# ETH-PHY.net
KiCad netlist of a schematic drawn in Altium Designer
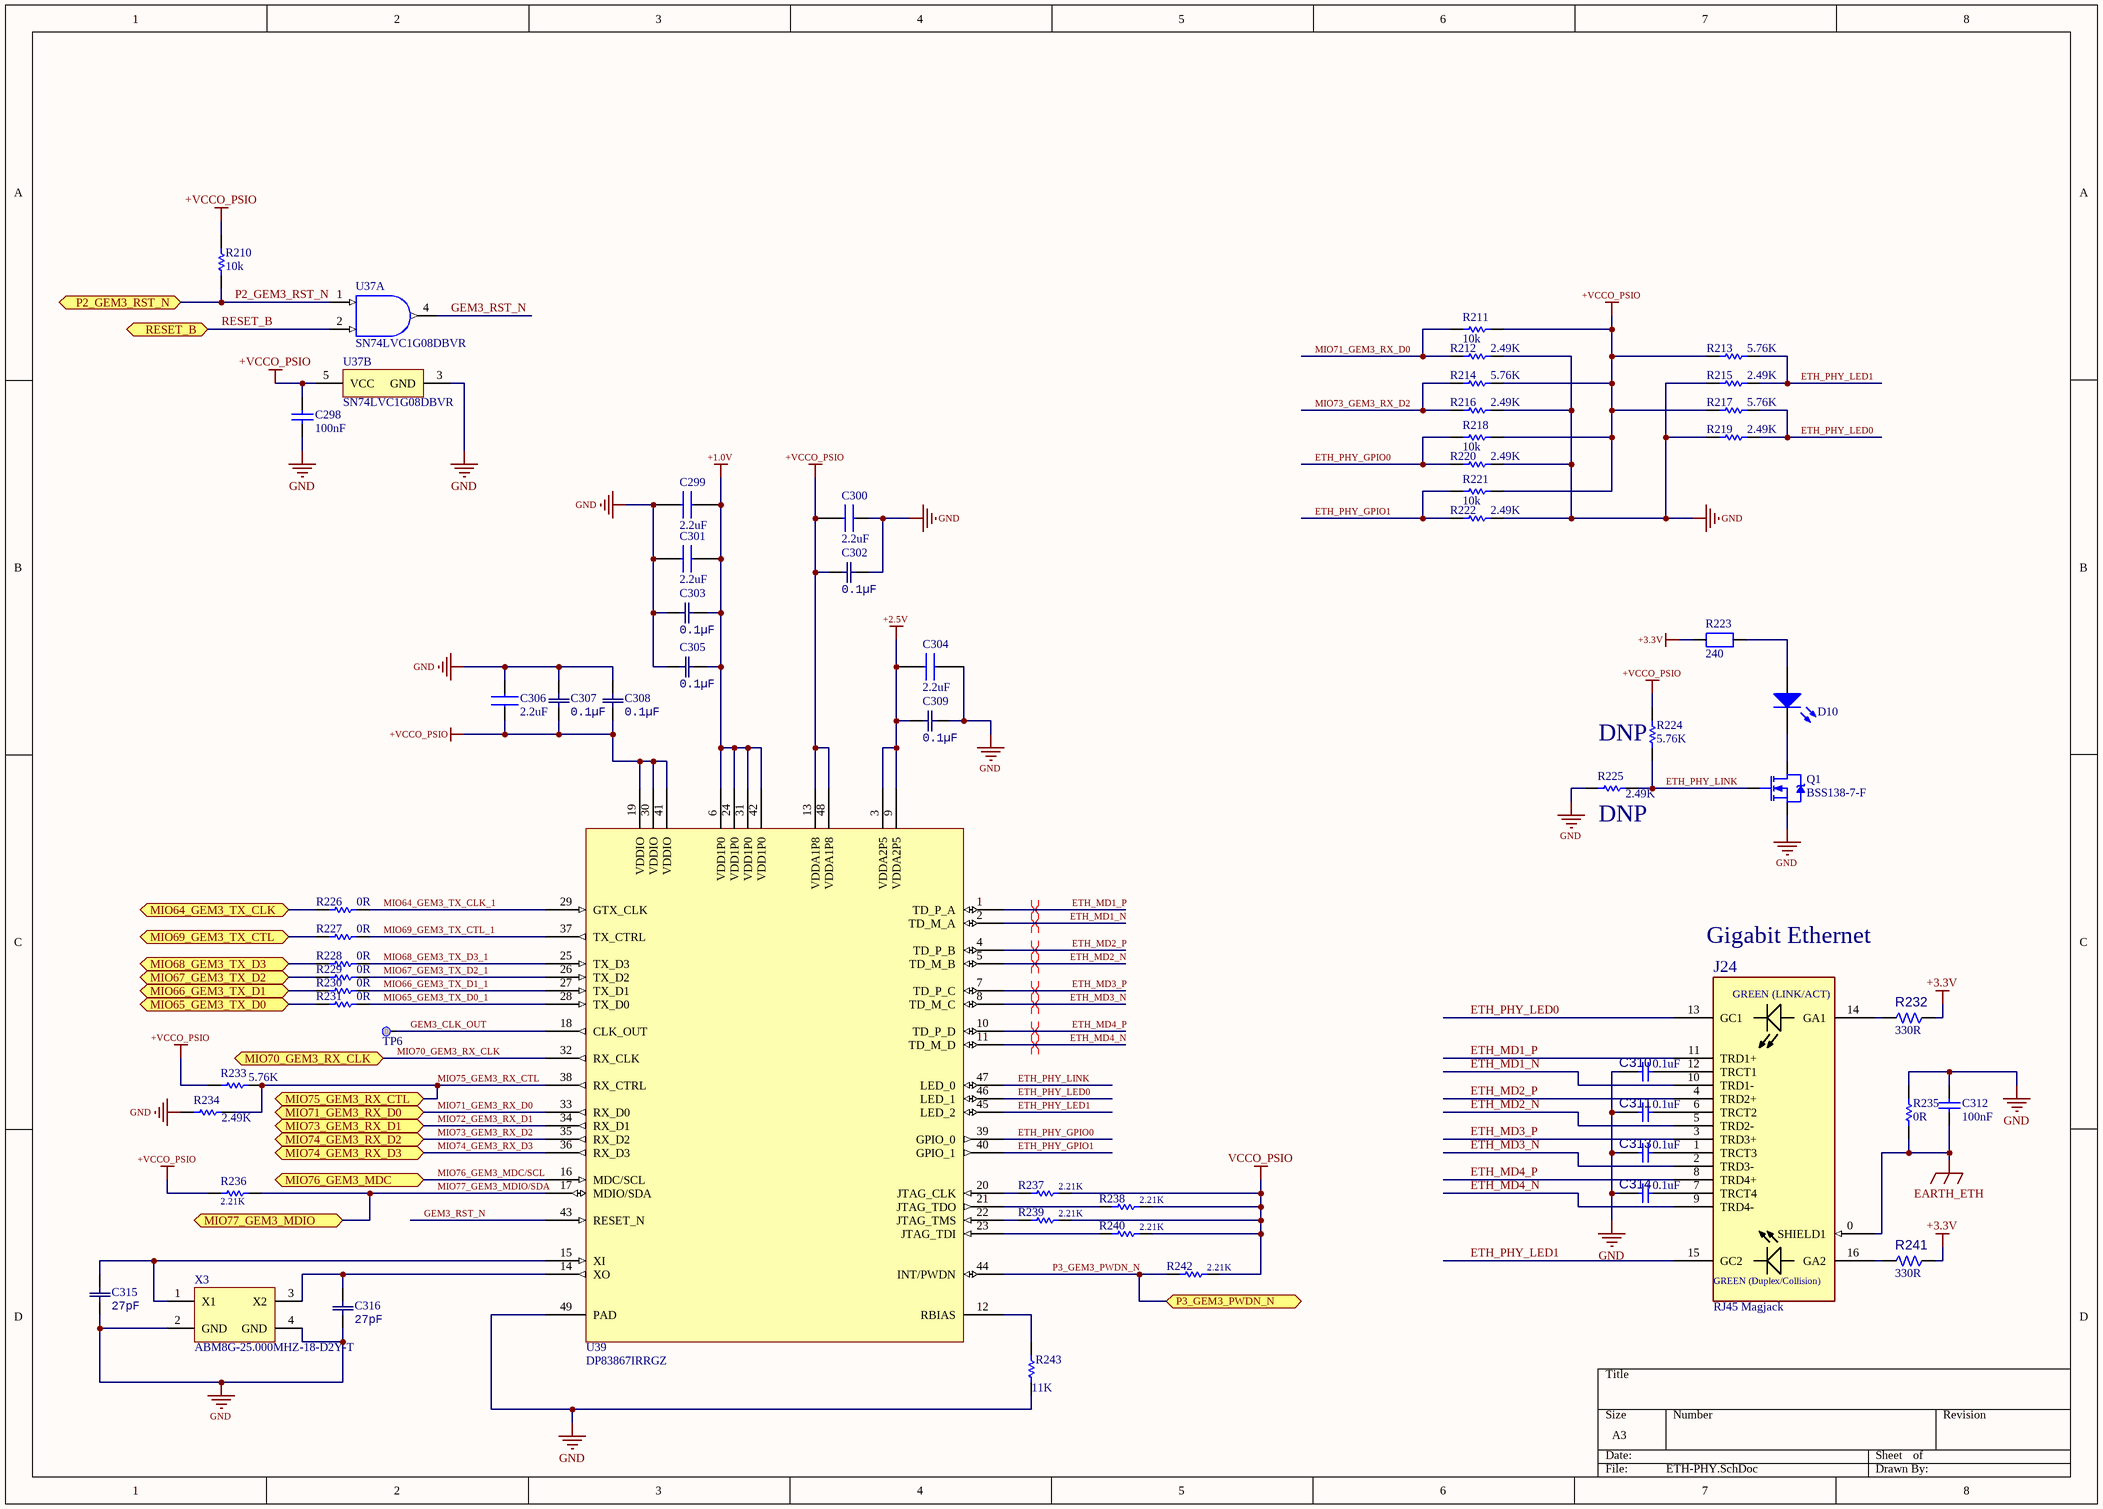
[diagram p0: ETH-PHY.SchDoc]

(export (version "E")
  (design (tool "Eeschema 10.0.6"))
  (components
    (comp (ref "C298")
      (value "100nF")
      (footprint "CAPC1005L_0402")
      (description "CAP CER 0.1UF 25V X7R 0402")
      (fields (field (name "VOLTAGE") "25V") (field (name "TOLERANCE") "10%"))
      (libsource (lib "Ultrascale_SchLib") (part "CAPCER0402X7R100N25V_10T"))
    )
    (comp (ref "C299")
      (value "2.2uF")
      (footprint "CAPC0603X33N")
      (description "Multilayer Ceramic Capacitors MLCC - SMD/SMT 0201 2.2uF 10volts *Derate Voltage/Temp")
      (fields (field (name "MANUFACTURER_PART_NUMBER") "GRM033R61A225KE47D"))
      (libsource (lib "Ultrascale_SchLib") (part "GRM033R61A225KE47D"))
    )
    (comp (ref "C300")
      (value "2.2uF")
      (footprint "CAPC0603X33N")
      (description "Multilayer Ceramic Capacitors MLCC - SMD/SMT 0201 2.2uF 10volts *Derate Voltage/Temp")
      (fields (field (name "MANUFACTURER_PART_NUMBER") "GRM033R61A225KE47D"))
      (libsource (lib "Ultrascale_SchLib") (part "GRM033R61A225KE47D"))
    )
    (comp (ref "C301")
      (value "2.2uF")
      (footprint "CAPC0603X33N")
      (description "Multilayer Ceramic Capacitors MLCC - SMD/SMT 0201 2.2uF 10volts *Derate Voltage/Temp")
      (fields (field (name "MANUFACTURER_PART_NUMBER") "GRM033R61A225KE47D"))
      (libsource (lib "Ultrascale_SchLib") (part "GRM033R61A225KE47D"))
    )
    (comp (ref "C302")
      (value "0.1µF")
      (footprint "CAP_0603")
      (description "CAP CER 0.1UF 25V 10% X5R 0201")
      (fields
        (field (name "MANUFACTURER_PART_NUMBER") "C0603X5R1E104K030BB")
        (field (name "DIGI-KEY PART NUMBER") "445-13671-1-ND")
      )
      (libsource (lib "Ultrascale_SchLib") (part "C0603X5R1E104K030BB"))
    )
    (comp (ref "C303")
      (value "0.1µF")
      (footprint "CAP_0603")
      (description "CAP CER 0.1UF 25V 10% X5R 0201")
      (fields
        (field (name "MANUFACTURER_PART_NUMBER") "C0603X5R1E104K030BB")
        (field (name "DIGI-KEY PART NUMBER") "445-13671-1-ND")
      )
      (libsource (lib "Ultrascale_SchLib") (part "C0603X5R1E104K030BB"))
    )
    (comp (ref "C304")
      (value "2.2uF")
      (footprint "CAPC0603X33N")
      (description "Multilayer Ceramic Capacitors MLCC - SMD/SMT 0201 2.2uF 10volts *Derate Voltage/Temp")
      (fields (field (name "MANUFACTURER_PART_NUMBER") "GRM033R61A225KE47D"))
      (libsource (lib "Ultrascale_SchLib") (part "GRM033R61A225KE47D"))
    )
    (comp (ref "C305")
      (value "0.1µF")
      (footprint "CAP_0603")
      (description "CAP CER 0.1UF 25V 10% X5R 0201")
      (fields
        (field (name "MANUFACTURER_PART_NUMBER") "C0603X5R1E104K030BB")
        (field (name "DIGI-KEY PART NUMBER") "445-13671-1-ND")
      )
      (libsource (lib "Ultrascale_SchLib") (part "C0603X5R1E104K030BB"))
    )
    (comp (ref "C306")
      (value "2.2uF")
      (footprint "CAPC0603X33N")
      (description "Multilayer Ceramic Capacitors MLCC - SMD/SMT 0201 2.2uF 10volts *Derate Voltage/Temp")
      (fields (field (name "MANUFACTURER_PART_NUMBER") "GRM033R61A225KE47D"))
      (libsource (lib "Ultrascale_SchLib") (part "GRM033R61A225KE47D"))
    )
    (comp (ref "C307")
      (value "0.1µF")
      (footprint "CAP_0603")
      (description "CAP CER 0.1UF 25V 10% X5R 0201")
      (fields
        (field (name "MANUFACTURER_PART_NUMBER") "C0603X5R1E104K030BB")
        (field (name "DIGI-KEY PART NUMBER") "445-13671-1-ND")
      )
      (libsource (lib "Ultrascale_SchLib") (part "C0603X5R1E104K030BB"))
    )
    (comp (ref "C308")
      (value "0.1µF")
      (footprint "CAP_0603")
      (description "CAP CER 0.1UF 25V 10% X5R 0201")
      (fields
        (field (name "MANUFACTURER_PART_NUMBER") "C0603X5R1E104K030BB")
        (field (name "DIGI-KEY PART NUMBER") "445-13671-1-ND")
      )
      (libsource (lib "Ultrascale_SchLib") (part "C0603X5R1E104K030BB"))
    )
    (comp (ref "C309")
      (value "0.1µF")
      (footprint "CAP_0603")
      (description "CAP CER 0.1UF 25V 10% X5R 0201")
      (fields
        (field (name "MANUFACTURER_PART_NUMBER") "C0603X5R1E104K030BB")
        (field (name "DIGI-KEY PART NUMBER") "445-13671-1-ND")
      )
      (libsource (lib "Ultrascale_SchLib") (part "C0603X5R1E104K030BB"))
    )
    (comp (ref "C310")
      (value "0.1uF")
      (footprint "Ultrascale_PcbLib:CAP_C_0402")
      (description "Capacitor")
      (fields
        (field (name "VOLTAGE") "50V")
        (field (name "TOLERANCE") "10%")
        (field (name "OWNER") "Jamus Griego")
      )
      (libsource (lib "Ultrascale_SchLib") (part "Capacitor NP"))
    )
    (comp (ref "C311")
      (value "0.1uF")
      (footprint "Ultrascale_PcbLib:CAP_C_0402")
      (description "Capacitor")
      (fields
        (field (name "VOLTAGE") "50V")
        (field (name "TOLERANCE") "10%")
        (field (name "OWNER") "Jamus Griego")
      )
      (libsource (lib "Ultrascale_SchLib") (part "Capacitor NP"))
    )
    (comp (ref "C312")
      (value "100nF")
      (footprint "CAPC1005L_0402")
      (description "CAP CER 0.1UF 25V X7R 0402")
      (fields (field (name "VOLTAGE") "25V") (field (name "TOLERANCE") "10%"))
      (libsource (lib "Ultrascale_SchLib") (part "CAPCER0402X7R100N25V_10T"))
    )
    (comp (ref "C313")
      (value "0.1uF")
      (footprint "Ultrascale_PcbLib:CAP_C_0402")
      (description "Capacitor")
      (fields
        (field (name "VOLTAGE") "50V")
        (field (name "TOLERANCE") "10%")
        (field (name "OWNER") "Jamus Griego")
      )
      (libsource (lib "Ultrascale_SchLib") (part "Capacitor NP"))
    )
    (comp (ref "C314")
      (value "0.1uF")
      (footprint "Ultrascale_PcbLib:CAP_C_0402")
      (description "Capacitor")
      (fields
        (field (name "VOLTAGE") "50V")
        (field (name "TOLERANCE") "10%")
        (field (name "OWNER") "Jamus Griego")
      )
      (libsource (lib "Ultrascale_SchLib") (part "Capacitor NP"))
    )
    (comp (ref "C315")
      (value "27pF")
      (footprint "CAP_0603")
      (description "CAP CER 0.1UF 25V 10% X5R 0201")
      (fields
        (field (name "MANUFACTURER_PART_NUMBER") "C0603X5R1E104K030BB")
        (field (name "DIGI-KEY PART NUMBER") "445-13671-1-ND")
      )
      (libsource (lib "Ultrascale_SchLib") (part "C0603X5R1E104K030BB"))
    )
    (comp (ref "C316")
      (value "27pF")
      (footprint "CAP_0603")
      (description "CAP CER 0.1UF 25V 10% X5R 0201")
      (fields
        (field (name "MANUFACTURER_PART_NUMBER") "C0603X5R1E104K030BB")
        (field (name "DIGI-KEY PART NUMBER") "445-13671-1-ND")
      )
      (libsource (lib "Ultrascale_SchLib") (part "C0603X5R1E104K030BB"))
    )
    (comp (ref "D10")
      (value "~")
      (footprint "LED0603BLUE")
      (description "LED BLUE DIFFUSED 0603 SMD")
      (libsource (lib "Ultrascale_SchLib") (part "LED0603BLUE"))
    )
    (comp (ref "J24")
      (value "RJ45 Magjack")
      (footprint "Ultrascale_PcbLib:CON_MODULAR_RJ45_TH_RA_RJMG2012211A0FR")
      (description "CON RJ-45 RJMG2012211A0FR")
      (libsource (lib "Ultrascale_SchLib") (part "CON RJ-45 RJMG2012211A0FR"))
    )
    (comp (ref "Q1")
      (value "BSS138-7-F")
      (footprint "DIODES_SOT23")
      (description "MOSFET N-CH 50V 200MA SOT23-3")
      (libsource (lib "Ultrascale_SchLib") (part "BSS138-7-F"))
    )
    (comp (ref "R210")
      (value "10k")
      (footprint "RESC1005L_0402")
      (description "RES SMD 10K OHM 0.5% 1/16W 0402")
      (fields (field (name "POWER") "1/16W") (field (name "TOLERANCE") "0.5%"))
      (libsource (lib "Ultrascale_SchLib") (part "RES0402_10K_0W1_05T"))
    )
    (comp (ref "R211")
      (value "10k")
      (footprint "RESC1005L_0402")
      (description "RES SMD 10K OHM 0.5% 1/16W 0402")
      (fields (field (name "POWER") "1/16W") (field (name "TOLERANCE") "0.5%"))
      (libsource (lib "Ultrascale_SchLib") (part "RES0402_10K_0W1_05T"))
    )
    (comp (ref "R212")
      (value "2.49K")
      (footprint "RC0201N")
      (description "RES 2.49K OHM 0201 1% 1/20W")
      (fields
        (field (name "DIGI-KEY PART NUMBER") "541-2.49KAABCT-ND")
        (field (name "MANUFACTURER_PART_NUMBER") "CRCW02012K49FKED")
        (field (name "COPYRIGHT") "Copyright (C) 2015 Accelerated Designs. All rights reserved")
      )
      (libsource (lib "Ultrascale_SchLib") (part "CRCW02012K49FKED"))
    )
    (comp (ref "R213")
      (value "ERJ-1GEF5761C")
      (footprint "RC0201N")
      (description "RES 5.76K OHM 0201 1% 1/20W")
      (fields
        (field (name "DIGIKEYPARTNUMBER") "P4.70KABTR-ND")
        (field (name "TOLERANCE") "Â±1%")
        (field (name "RESISTANCE_(OHMS)") "5.76K")
        (field (name "COPYRIGHT") "Copyright (C) 2015 Accelerated Designs. All rights reserved")
      )
      (libsource (lib "Ultrascale_SchLib") (part "ERJ-1GEF5761C"))
    )
    (comp (ref "R214")
      (value "ERJ-1GEF5761C")
      (footprint "RC0201N")
      (description "RES 5.76K OHM 0201 1% 1/20W")
      (fields
        (field (name "DIGIKEYPARTNUMBER") "P4.70KABTR-ND")
        (field (name "TOLERANCE") "Â±1%")
        (field (name "RESISTANCE_(OHMS)") "5.76K")
        (field (name "COPYRIGHT") "Copyright (C) 2015 Accelerated Designs. All rights reserved")
      )
      (libsource (lib "Ultrascale_SchLib") (part "ERJ-1GEF5761C"))
    )
    (comp (ref "R215")
      (value "2.49K")
      (footprint "RC0201N")
      (description "RES 2.49K OHM 0201 1% 1/20W")
      (fields
        (field (name "DIGI-KEY PART NUMBER") "541-2.49KAABCT-ND")
        (field (name "MANUFACTURER_PART_NUMBER") "CRCW02012K49FKED")
        (field (name "COPYRIGHT") "Copyright (C) 2015 Accelerated Designs. All rights reserved")
      )
      (libsource (lib "Ultrascale_SchLib") (part "CRCW02012K49FKED"))
    )
    (comp (ref "R216")
      (value "2.49K")
      (footprint "RC0201N")
      (description "RES 2.49K OHM 0201 1% 1/20W")
      (fields
        (field (name "DIGI-KEY PART NUMBER") "541-2.49KAABCT-ND")
        (field (name "MANUFACTURER_PART_NUMBER") "CRCW02012K49FKED")
        (field (name "COPYRIGHT") "Copyright (C) 2015 Accelerated Designs. All rights reserved")
      )
      (libsource (lib "Ultrascale_SchLib") (part "CRCW02012K49FKED"))
    )
    (comp (ref "R217")
      (value "ERJ-1GEF5761C")
      (footprint "RC0201N")
      (description "RES 5.76K OHM 0201 1% 1/20W")
      (fields
        (field (name "DIGIKEYPARTNUMBER") "P4.70KABTR-ND")
        (field (name "TOLERANCE") "Â±1%")
        (field (name "RESISTANCE_(OHMS)") "5.76K")
        (field (name "COPYRIGHT") "Copyright (C) 2015 Accelerated Designs. All rights reserved")
      )
      (libsource (lib "Ultrascale_SchLib") (part "ERJ-1GEF5761C"))
    )
    (comp (ref "R218")
      (value "10k")
      (footprint "RESC1005L_0402")
      (description "RES SMD 10K OHM 0.5% 1/16W 0402")
      (fields (field (name "POWER") "1/16W") (field (name "TOLERANCE") "0.5%"))
      (libsource (lib "Ultrascale_SchLib") (part "RES0402_10K_0W1_05T"))
    )
    (comp (ref "R219")
      (value "2.49K")
      (footprint "RC0201N")
      (description "RES 2.49K OHM 0201 1% 1/20W")
      (fields
        (field (name "DIGI-KEY PART NUMBER") "541-2.49KAABCT-ND")
        (field (name "MANUFACTURER_PART_NUMBER") "CRCW02012K49FKED")
        (field (name "COPYRIGHT") "Copyright (C) 2015 Accelerated Designs. All rights reserved")
      )
      (libsource (lib "Ultrascale_SchLib") (part "CRCW02012K49FKED"))
    )
    (comp (ref "R220")
      (value "2.49K")
      (footprint "RC0201N")
      (description "RES 2.49K OHM 0201 1% 1/20W")
      (fields
        (field (name "DIGI-KEY PART NUMBER") "541-2.49KAABCT-ND")
        (field (name "MANUFACTURER_PART_NUMBER") "CRCW02012K49FKED")
        (field (name "COPYRIGHT") "Copyright (C) 2015 Accelerated Designs. All rights reserved")
      )
      (libsource (lib "Ultrascale_SchLib") (part "CRCW02012K49FKED"))
    )
    (comp (ref "R221")
      (value "10k")
      (footprint "RESC1005L_0402")
      (description "RES SMD 10K OHM 0.5% 1/16W 0402")
      (fields (field (name "POWER") "1/16W") (field (name "TOLERANCE") "0.5%"))
      (libsource (lib "Ultrascale_SchLib") (part "RES0402_10K_0W1_05T"))
    )
    (comp (ref "R222")
      (value "2.49K")
      (footprint "RC0201N")
      (description "RES 2.49K OHM 0201 1% 1/20W")
      (fields
        (field (name "DIGI-KEY PART NUMBER") "541-2.49KAABCT-ND")
        (field (name "MANUFACTURER_PART_NUMBER") "CRCW02012K49FKED")
        (field (name "COPYRIGHT") "Copyright (C) 2015 Accelerated Designs. All rights reserved")
      )
      (libsource (lib "Ultrascale_SchLib") (part "CRCW02012K49FKED"))
    )
    (comp (ref "R223")
      (value "240")
      (footprint "RESC0603X28N")
      (description "VISHAY - CRCW0201240RFNED - RES, THICK FILM, 240R, 1%, 0.05W, 0201")
      (fields (field (name "MANUFACTURER_PART_NUMBER") "CRCW0201240RFNED"))
      (libsource (lib "Ultrascale_SchLib") (part "CRCW0201240RFNED"))
    )
    (comp (ref "R224")
      (value "ERJ-1GEF5761C")
      (footprint "RC0201N")
      (description "RES 5.76K OHM 0201 1% 1/20W")
      (fields
        (field (name "DIGIKEYPARTNUMBER") "P4.70KABTR-ND")
        (field (name "TOLERANCE") "Â±1%")
        (field (name "RESISTANCE_(OHMS)") "5.76K")
        (field (name "COPYRIGHT") "Copyright (C) 2015 Accelerated Designs. All rights reserved")
      )
      (libsource (lib "Ultrascale_SchLib") (part "ERJ-1GEF5761C"))
    )
    (comp (ref "R225")
      (value "2.49K")
      (footprint "RC0201N")
      (description "RES 2.49K OHM 0201 1% 1/20W")
      (fields
        (field (name "DIGI-KEY PART NUMBER") "541-2.49KAABCT-ND")
        (field (name "MANUFACTURER_PART_NUMBER") "CRCW02012K49FKED")
        (field (name "COPYRIGHT") "Copyright (C) 2015 Accelerated Designs. All rights reserved")
      )
      (libsource (lib "Ultrascale_SchLib") (part "CRCW02012K49FKED"))
    )
    (comp (ref "R226")
      (value "0R")
      (footprint "RESC1005L_0402")
      (description "RES SMD 0 OHM JUMPER 1/16W 0402")
      (fields (field (name "POWER") "0.063W, 1/16W") (field (name "Comment") "RES0402_0R"))
      (libsource (lib "Ultrascale_SchLib") (part "RES0402_0R"))
    )
    (comp (ref "R227")
      (value "0R")
      (footprint "RESC1005L_0402")
      (description "RES SMD 0 OHM JUMPER 1/16W 0402")
      (fields (field (name "POWER") "0.063W, 1/16W") (field (name "Comment") "RES0402_0R"))
      (libsource (lib "Ultrascale_SchLib") (part "RES0402_0R"))
    )
    (comp (ref "R228")
      (value "0R")
      (footprint "RESC1005L_0402")
      (description "RES SMD 0 OHM JUMPER 1/16W 0402")
      (fields (field (name "POWER") "0.063W, 1/16W") (field (name "Comment") "RES0402_0R"))
      (libsource (lib "Ultrascale_SchLib") (part "RES0402_0R"))
    )
    (comp (ref "R229")
      (value "0R")
      (footprint "RESC1005L_0402")
      (description "RES SMD 0 OHM JUMPER 1/16W 0402")
      (fields (field (name "POWER") "0.063W, 1/16W") (field (name "Comment") "RES0402_0R"))
      (libsource (lib "Ultrascale_SchLib") (part "RES0402_0R"))
    )
    (comp (ref "R230")
      (value "0R")
      (footprint "RESC1005L_0402")
      (description "RES SMD 0 OHM JUMPER 1/16W 0402")
      (fields (field (name "POWER") "0.063W, 1/16W") (field (name "Comment") "RES0402_0R"))
      (libsource (lib "Ultrascale_SchLib") (part "RES0402_0R"))
    )
    (comp (ref "R231")
      (value "0R")
      (footprint "RESC1005L_0402")
      (description "RES SMD 0 OHM JUMPER 1/16W 0402")
      (fields (field (name "POWER") "0.063W, 1/16W") (field (name "Comment") "RES0402_0R"))
      (libsource (lib "Ultrascale_SchLib") (part "RES0402_0R"))
    )
    (comp (ref "R232")
      (value "330R")
      (footprint "Ultrascale_PcbLib:RES_C_0603")
      (description "Resistor")
      (fields (field (name "TOLERANCE") "5%") (field (name "VOLTAGE") "75V"))
      (libsource (lib "Ultrascale_SchLib") (part "Resistor"))
    )
    (comp (ref "R233")
      (value "ERJ-1GEF5761C")
      (footprint "RC0201N")
      (description "RES 5.76K OHM 0201 1% 1/20W")
      (fields
        (field (name "DIGIKEYPARTNUMBER") "P4.70KABTR-ND")
        (field (name "TOLERANCE") "Â±1%")
        (field (name "RESISTANCE_(OHMS)") "5.76K")
        (field (name "COPYRIGHT") "Copyright (C) 2015 Accelerated Designs. All rights reserved")
      )
      (libsource (lib "Ultrascale_SchLib") (part "ERJ-1GEF5761C"))
    )
    (comp (ref "R234")
      (value "2.49K")
      (footprint "RC0201N")
      (description "RES 2.49K OHM 0201 1% 1/20W")
      (fields
        (field (name "DIGI-KEY PART NUMBER") "541-2.49KAABCT-ND")
        (field (name "MANUFACTURER_PART_NUMBER") "CRCW02012K49FKED")
        (field (name "COPYRIGHT") "Copyright (C) 2015 Accelerated Designs. All rights reserved")
      )
      (libsource (lib "Ultrascale_SchLib") (part "CRCW02012K49FKED"))
    )
    (comp (ref "R235")
      (value "0R")
      (footprint "RESC1005L_0402")
      (description "RES SMD 0 OHM JUMPER 1/10W 0402")
      (fields (field (name "POWER") "1/10W") (field (name "Comment") "RES0402_0R_0W1"))
      (libsource (lib "Ultrascale_SchLib") (part "RES0402_0R_0W1"))
    )
    (comp (ref "R236")
      (value "2.21K")
      (footprint "RC0201N")
      (description "RES 2.21K OHM 0201 1% 1/20W")
      (fields
        (field (name "DIGIKEYPARTNUMBER") "P0.0AGTR-ND")
        (field (name "MANUFACTURER_PART_NUMBER") "ERJ-1GEF2211C")
        (field (name "COPYRIGHT") "Copyright (C) 2015 Accelerated Designs. All rights reserved")
      )
      (libsource (lib "Ultrascale_SchLib") (part "ERJ-1GEF2211C"))
    )
    (comp (ref "R237")
      (value "2.21K")
      (footprint "RC0201N")
      (description "RES 2.21K OHM 0201 1% 1/20W")
      (fields
        (field (name "DIGIKEYPARTNUMBER") "P0.0AGTR-ND")
        (field (name "MANUFACTURER_PART_NUMBER") "ERJ-1GEF2211C")
        (field (name "COPYRIGHT") "Copyright (C) 2015 Accelerated Designs. All rights reserved")
      )
      (libsource (lib "Ultrascale_SchLib") (part "ERJ-1GEF2211C"))
    )
    (comp (ref "R238")
      (value "2.21K")
      (footprint "RC0201N")
      (description "RES 2.21K OHM 0201 1% 1/20W")
      (fields
        (field (name "DIGIKEYPARTNUMBER") "P0.0AGTR-ND")
        (field (name "MANUFACTURER_PART_NUMBER") "ERJ-1GEF2211C")
        (field (name "COPYRIGHT") "Copyright (C) 2015 Accelerated Designs. All rights reserved")
      )
      (libsource (lib "Ultrascale_SchLib") (part "ERJ-1GEF2211C"))
    )
    (comp (ref "R239")
      (value "2.21K")
      (footprint "RC0201N")
      (description "RES 2.21K OHM 0201 1% 1/20W")
      (fields
        (field (name "DIGIKEYPARTNUMBER") "P0.0AGTR-ND")
        (field (name "MANUFACTURER_PART_NUMBER") "ERJ-1GEF2211C")
        (field (name "COPYRIGHT") "Copyright (C) 2015 Accelerated Designs. All rights reserved")
      )
      (libsource (lib "Ultrascale_SchLib") (part "ERJ-1GEF2211C"))
    )
    (comp (ref "R240")
      (value "2.21K")
      (footprint "RC0201N")
      (description "RES 2.21K OHM 0201 1% 1/20W")
      (fields
        (field (name "DIGIKEYPARTNUMBER") "P0.0AGTR-ND")
        (field (name "MANUFACTURER_PART_NUMBER") "ERJ-1GEF2211C")
        (field (name "COPYRIGHT") "Copyright (C) 2015 Accelerated Designs. All rights reserved")
      )
      (libsource (lib "Ultrascale_SchLib") (part "ERJ-1GEF2211C"))
    )
    (comp (ref "R241")
      (value "330R")
      (footprint "Ultrascale_PcbLib:RES_C_0603")
      (description "Resistor")
      (fields (field (name "TOLERANCE") "5%") (field (name "VOLTAGE") "75V"))
      (libsource (lib "Ultrascale_SchLib") (part "Resistor"))
    )
    (comp (ref "R242")
      (value "2.21K")
      (footprint "RC0201N")
      (description "RES 2.21K OHM 0201 1% 1/20W")
      (fields
        (field (name "DIGIKEYPARTNUMBER") "P0.0AGTR-ND")
        (field (name "MANUFACTURER_PART_NUMBER") "ERJ-1GEF2211C")
        (field (name "COPYRIGHT") "Copyright (C) 2015 Accelerated Designs. All rights reserved")
      )
      (libsource (lib "Ultrascale_SchLib") (part "ERJ-1GEF2211C"))
    )
    (comp (ref "R243")
      (value "11K")
      (footprint "RES_V0201")
      (description "RES 11.0K OHM 0201 1% 1/20W")
      (fields
        (field (name "MANUFACTURER_PART_NUMBER") "CRCW020111K0FKED")
        (field (name "COPYRIGHT") "Copyright (C) 2015 Accelerated Designs. All rights reserved")
      )
      (libsource (lib "Ultrascale_SchLib") (part "CRCW020111K0FKED"))
    )
    (comp (ref "TP6")
      (value "TP")
      (footprint "TP")
      (description "Test Point")
      (libsource (lib "Ultrascale_SchLib") (part "Test Point"))
    )
    (comp (ref "U37")
      (value "SN74LVC1G08DBVR")
      (footprint "DBV0005A_N")
      (description "Single 2-Input Positive-AND Gate, DBV0005A, LARGE T&R")
      (fields (field (name "GENERIC PART NUMBER") "SN74LVC1G08"))
      (libsource (lib "Ultrascale_SchLib") (part "SN74LVC1G08DBVR"))
    )
    (comp (ref "U39")
      (value "DP83867IRRGZ")
      (footprint "QFN50P700X700X100_HS-49N")
      (description "IC ETHERNET PHY 48VQFN")
      (libsource (lib "Ultrascale_SchLib") (part "DP83867IRRGZ"))
    )
    (comp (ref "X3")
      (value "ABM8G-25.000MHZ-18-D2Y-T")
      (footprint "ABM8G")
      (description "CRYSTAL 25.0000MHZ 18PF SMD")
      (libsource (lib "Ultrascale_SchLib") (part "ABM8G-25.000MHZ-18-D2Y-T"))
    )
  )
  (nets
    (net (code "1") (name "+1.0V") (class "Default")
      (node (ref "C299") (pin "1") (pinfunction "1_1") (pintype "passive"))
      (node (ref "C301") (pin "1") (pinfunction "1_1") (pintype "passive"))
      (node (ref "C303") (pin "2") (pinfunction "2_2") (pintype "passive"))
      (node (ref "C305") (pin "1") (pinfunction "1_1") (pintype "passive"))
      (node (ref "U39") (pin "24") (pinfunction "VDD1P0_24") (pintype "passive"))
      (node (ref "U39") (pin "31") (pinfunction "VDD1P0_31") (pintype "passive"))
      (node (ref "U39") (pin "42") (pinfunction "VDD1P0_42") (pintype "passive"))
      (node (ref "U39") (pin "6") (pinfunction "VDD1P0_6") (pintype "passive"))
    )
    (net (code "2") (name "+2.5V") (class "Default")
      (node (ref "C304") (pin "2") (pinfunction "2_2") (pintype "passive"))
      (node (ref "C309") (pin "1") (pinfunction "1_1") (pintype "passive"))
      (node (ref "U39") (pin "3") (pinfunction "VDDA2P5_3") (pintype "passive"))
      (node (ref "U39") (pin "9") (pinfunction "VDDA2P5_9") (pintype "passive"))
    )
    (net (code "3") (name "+3.3V") (class "Default")
      (node (ref "R223") (pin "1") (pinfunction "1_1") (pintype "passive"))
      (node (ref "R232") (pin "2") (pinfunction "2_2") (pintype "passive"))
      (node (ref "R241") (pin "2") (pinfunction "2_2") (pintype "passive"))
    )
    (net (code "4") (name "+VCCO_PSIO") (class "Default")
      (node (ref "C298") (pin "1") (pinfunction "1_1") (pintype "passive"))
      (node (ref "C300") (pin "2") (pinfunction "2_2") (pintype "passive"))
      (node (ref "C302") (pin "1") (pinfunction "1_1") (pintype "passive"))
      (node (ref "C306") (pin "1") (pinfunction "1_1") (pintype "passive"))
      (node (ref "C307") (pin "1") (pinfunction "1_1") (pintype "passive"))
      (node (ref "C308") (pin "1") (pinfunction "1_1") (pintype "passive"))
      (node (ref "R210") (pin "2") (pinfunction "2_2") (pintype "passive"))
      (node (ref "R211") (pin "2") (pinfunction "2_2") (pintype "passive"))
      (node (ref "R213") (pin "1") (pinfunction "1_1") (pintype "passive"))
      (node (ref "R214") (pin "2") (pinfunction "2_2") (pintype "passive"))
      (node (ref "R217") (pin "1") (pinfunction "1_1") (pintype "passive"))
      (node (ref "R218") (pin "2") (pinfunction "2_2") (pintype "passive"))
      (node (ref "R221") (pin "2") (pinfunction "2_2") (pintype "passive"))
      (node (ref "R224") (pin "2") (pinfunction "2_2") (pintype "passive"))
      (node (ref "R233") (pin "1") (pinfunction "1_1") (pintype "passive"))
      (node (ref "R236") (pin "1") (pinfunction "1_1") (pintype "passive"))
      (node (ref "U37") (pin "5") (pinfunction "VCC_5") (pintype "power_in"))
      (node (ref "U39") (pin "13") (pinfunction "VDDA1P8_13") (pintype "passive"))
      (node (ref "U39") (pin "19") (pinfunction "VDDIO_19") (pintype "passive"))
      (node (ref "U39") (pin "30") (pinfunction "VDDIO_30") (pintype "passive"))
      (node (ref "U39") (pin "41") (pinfunction "VDDIO_41") (pintype "passive"))
      (node (ref "U39") (pin "48") (pinfunction "VDDA1P8_48") (pintype "passive"))
    )
    (net (code "5") (name "/ETH_MD1_N") (class "Default")
      (node (ref "J24") (pin "10") (pinfunction "TRD1-_10") (pintype "passive"))
      (node (ref "U39") (pin "2") (pinfunction "TD_M_A_2") (pintype "bidirectional"))
    )
    (net (code "6") (name "/ETH_MD1_P") (class "Default")
      (node (ref "J24") (pin "11") (pinfunction "TRD1+_11") (pintype "passive"))
      (node (ref "U39") (pin "1") (pinfunction "TD_P_A_1") (pintype "bidirectional"))
    )
    (net (code "7") (name "/ETH_MD2_N") (class "Default")
      (node (ref "J24") (pin "5") (pinfunction "TRD2-_5") (pintype "passive"))
      (node (ref "U39") (pin "5") (pinfunction "TD_M_B_5") (pintype "bidirectional"))
    )
    (net (code "8") (name "/ETH_MD2_P") (class "Default")
      (node (ref "J24") (pin "4") (pinfunction "TRD2+_4") (pintype "passive"))
      (node (ref "U39") (pin "4") (pinfunction "TD_P_B_4") (pintype "bidirectional"))
    )
    (net (code "9") (name "/ETH_MD3_N") (class "Default")
      (node (ref "J24") (pin "2") (pinfunction "TRD3-_2") (pintype "passive"))
      (node (ref "U39") (pin "8") (pinfunction "TD_M_C_8") (pintype "bidirectional"))
    )
    (net (code "10") (name "/ETH_MD3_P") (class "Default")
      (node (ref "J24") (pin "3") (pinfunction "TRD3+_3") (pintype "passive"))
      (node (ref "U39") (pin "7") (pinfunction "TD_P_C_7") (pintype "bidirectional"))
    )
    (net (code "11") (name "/ETH_MD4_N") (class "Default")
      (node (ref "J24") (pin "9") (pinfunction "TRD4-_9") (pintype "passive"))
      (node (ref "U39") (pin "11") (pinfunction "TD_M_D_11") (pintype "bidirectional"))
    )
    (net (code "12") (name "/ETH_MD4_P") (class "Default")
      (node (ref "J24") (pin "8") (pinfunction "TRD4+_8") (pintype "passive"))
      (node (ref "U39") (pin "10") (pinfunction "TD_P_D_10") (pintype "bidirectional"))
    )
    (net (code "13") (name "/ETH_PHY_GPIO0") (class "Default")
      (node (ref "R218") (pin "1") (pinfunction "1_1") (pintype "passive"))
      (node (ref "R220") (pin "1") (pinfunction "1_1") (pintype "passive"))
      (node (ref "U39") (pin "39") (pinfunction "GPIO_0_39") (pintype "output"))
    )
    (net (code "14") (name "/ETH_PHY_GPIO1") (class "Default")
      (node (ref "R221") (pin "1") (pinfunction "1_1") (pintype "passive"))
      (node (ref "R222") (pin "1") (pinfunction "1_1") (pintype "passive"))
      (node (ref "U39") (pin "40") (pinfunction "GPIO_1_40") (pintype "output"))
    )
    (net (code "15") (name "/ETH_PHY_LED0") (class "Default")
      (node (ref "J24") (pin "13") (pinfunction "GC1_13") (pintype "passive"))
      (node (ref "R217") (pin "2") (pinfunction "2_2") (pintype "passive"))
      (node (ref "R219") (pin "2") (pinfunction "2_2") (pintype "passive"))
      (node (ref "U39") (pin "46") (pinfunction "LED_1_46") (pintype "bidirectional"))
    )
    (net (code "16") (name "/ETH_PHY_LED1") (class "Default")
      (node (ref "J24") (pin "15") (pinfunction "GC2_15") (pintype "passive"))
      (node (ref "R213") (pin "2") (pinfunction "2_2") (pintype "passive"))
      (node (ref "R215") (pin "2") (pinfunction "2_2") (pintype "passive"))
      (node (ref "U39") (pin "45") (pinfunction "LED_2_45") (pintype "bidirectional"))
    )
    (net (code "17") (name "/ETH_PHY_LINK") (class "Default")
      (node (ref "Q1") (pin "G") (pinfunction "G_G") (pintype "passive"))
      (node (ref "R224") (pin "1") (pinfunction "1_1") (pintype "passive"))
      (node (ref "R225") (pin "2") (pinfunction "2_2") (pintype "passive"))
      (node (ref "U39") (pin "47") (pinfunction "LED_0_47") (pintype "bidirectional"))
    )
    (net (code "18") (name "/GEM3_CLK_OUT") (class "Default")
      (node (ref "TP6") (pin "1") (pinfunction "1_1") (pintype "passive"))
      (node (ref "U39") (pin "18") (pinfunction "CLK_OUT_18") (pintype "output"))
    )
    (net (code "19") (name "/GEM3_RST_N") (class "Default")
      (node (ref "U37") (pin "4") (pinfunction "Y_4") (pintype "output"))
      (node (ref "U39") (pin "43") (pinfunction "RESET_N_43") (pintype "input"))
    )
    (net (code "20") (name "/MIO64_GEM3_TX_CLK") (class "Default")
      (node (ref "R226") (pin "1") (pinfunction "1_1") (pintype "passive"))
    )
    (net (code "21") (name "/MIO64_GEM3_TX_CLK_1") (class "Default")
      (node (ref "R226") (pin "2") (pinfunction "2_2") (pintype "passive"))
      (node (ref "U39") (pin "29") (pinfunction "GTX_CLK_29") (pintype "input"))
    )
    (net (code "22") (name "/MIO65_GEM3_TX_D0") (class "Default")
      (node (ref "R231") (pin "1") (pinfunction "1_1") (pintype "passive"))
    )
    (net (code "23") (name "/MIO65_GEM3_TX_D0_1") (class "Default")
      (node (ref "R231") (pin "2") (pinfunction "2_2") (pintype "passive"))
      (node (ref "U39") (pin "28") (pinfunction "TX_D0_28") (pintype "input"))
    )
    (net (code "24") (name "/MIO66_GEM3_TX_D1") (class "Default")
      (node (ref "R230") (pin "1") (pinfunction "1_1") (pintype "passive"))
    )
    (net (code "25") (name "/MIO66_GEM3_TX_D1_1") (class "Default")
      (node (ref "R230") (pin "2") (pinfunction "2_2") (pintype "passive"))
      (node (ref "U39") (pin "27") (pinfunction "TX_D1_27") (pintype "input"))
    )
    (net (code "26") (name "/MIO67_GEM3_TX_D2") (class "Default")
      (node (ref "R229") (pin "1") (pinfunction "1_1") (pintype "passive"))
    )
    (net (code "27") (name "/MIO67_GEM3_TX_D2_1") (class "Default")
      (node (ref "R229") (pin "2") (pinfunction "2_2") (pintype "passive"))
      (node (ref "U39") (pin "26") (pinfunction "TX_D2_26") (pintype "input"))
    )
    (net (code "28") (name "/MIO68_GEM3_TX_D3") (class "Default")
      (node (ref "R228") (pin "1") (pinfunction "1_1") (pintype "passive"))
    )
    (net (code "29") (name "/MIO68_GEM3_TX_D3_1") (class "Default")
      (node (ref "R228") (pin "2") (pinfunction "2_2") (pintype "passive"))
      (node (ref "U39") (pin "25") (pinfunction "TX_D3_25") (pintype "input"))
    )
    (net (code "30") (name "/MIO69_GEM3_TX_CTL") (class "Default")
      (node (ref "R227") (pin "1") (pinfunction "1_1") (pintype "passive"))
    )
    (net (code "31") (name "/MIO69_GEM3_TX_CTL_1") (class "Default")
      (node (ref "R227") (pin "2") (pinfunction "2_2") (pintype "passive"))
      (node (ref "U39") (pin "37") (pinfunction "TX_CTRL_37") (pintype "output"))
    )
    (net (code "32") (name "/MIO70_GEM3_RX_CLK") (class "Default")
      (node (ref "U39") (pin "32") (pinfunction "RX_CLK_32") (pintype "output"))
    )
    (net (code "33") (name "/MIO71_GEM3_RX_D0") (class "Default")
      (node (ref "R211") (pin "1") (pinfunction "1_1") (pintype "passive"))
      (node (ref "R212") (pin "1") (pinfunction "1_1") (pintype "passive"))
      (node (ref "U39") (pin "33") (pinfunction "RX_D0_33") (pintype "output"))
    )
    (net (code "34") (name "/MIO72_GEM3_RX_D1") (class "Default")
      (node (ref "U39") (pin "34") (pinfunction "RX_D1_34") (pintype "output"))
    )
    (net (code "35") (name "/MIO73_GEM3_RX_D2") (class "Default")
      (node (ref "R214") (pin "1") (pinfunction "1_1") (pintype "passive"))
      (node (ref "R216") (pin "1") (pinfunction "1_1") (pintype "passive"))
      (node (ref "U39") (pin "35") (pinfunction "RX_D2_35") (pintype "output"))
    )
    (net (code "36") (name "/MIO74_GEM3_RX_D3") (class "Default")
      (node (ref "U39") (pin "36") (pinfunction "RX_D3_36") (pintype "output"))
    )
    (net (code "37") (name "/MIO75_GEM3_RX_CTL") (class "Default")
      (node (ref "R233") (pin "2") (pinfunction "2_2") (pintype "passive"))
      (node (ref "R234") (pin "2") (pinfunction "2_2") (pintype "passive"))
      (node (ref "U39") (pin "38") (pinfunction "RX_CTRL_38") (pintype "output"))
    )
    (net (code "38") (name "/MIO76_GEM3_MDC{slash}SCL") (class "Default")
      (node (ref "U39") (pin "16") (pinfunction "MDC/SCL_16") (pintype "input"))
    )
    (net (code "39") (name "/MIO77_GEM3_MDIO{slash}SDA") (class "Default")
      (node (ref "R236") (pin "2") (pinfunction "2_2") (pintype "passive"))
      (node (ref "U39") (pin "17") (pinfunction "MDIO/SDA_17") (pintype "bidirectional"))
    )
    (net (code "40") (name "/P2_GEM3_RST_N") (class "Default")
      (node (ref "R210") (pin "1") (pinfunction "1_1") (pintype "passive"))
      (node (ref "U37") (pin "1") (pinfunction "A_1") (pintype "input"))
    )
    (net (code "41") (name "/P3_GEM3_PWDN_N") (class "Default")
      (node (ref "R242") (pin "1") (pinfunction "1_1") (pintype "passive"))
      (node (ref "U39") (pin "44") (pinfunction "INT/PWDN_44") (pintype "bidirectional"))
    )
    (net (code "42") (name "/RESET_B") (class "Default")
      (node (ref "U37") (pin "2") (pinfunction "B_2") (pintype "input"))
    )
    (net (code "43") (name "EARTH_ETH") (class "Default")
      (node (ref "C312") (pin "2") (pinfunction "2_2") (pintype "passive"))
      (node (ref "J24") (pin "0") (pinfunction "SHIELD1_0") (pintype "input"))
      (node (ref "R235") (pin "1") (pinfunction "1_1") (pintype "passive"))
    )
    (net (code "44") (name "GND") (class "Default")
      (node (ref "C298") (pin "2") (pinfunction "2_2") (pintype "passive"))
      (node (ref "C299") (pin "2") (pinfunction "2_2") (pintype "passive"))
      (node (ref "C300") (pin "1") (pinfunction "1_1") (pintype "passive"))
      (node (ref "C301") (pin "2") (pinfunction "2_2") (pintype "passive"))
      (node (ref "C302") (pin "2") (pinfunction "2_2") (pintype "passive"))
      (node (ref "C303") (pin "1") (pinfunction "1_1") (pintype "passive"))
      (node (ref "C304") (pin "1") (pinfunction "1_1") (pintype "passive"))
      (node (ref "C305") (pin "2") (pinfunction "2_2") (pintype "passive"))
      (node (ref "C306") (pin "2") (pinfunction "2_2") (pintype "passive"))
      (node (ref "C307") (pin "2") (pinfunction "2_2") (pintype "passive"))
      (node (ref "C308") (pin "2") (pinfunction "2_2") (pintype "passive"))
      (node (ref "C309") (pin "2") (pinfunction "2_2") (pintype "passive"))
      (node (ref "C310") (pin "2") (pinfunction "2_2") (pintype "passive"))
      (node (ref "C311") (pin "2") (pinfunction "2_2") (pintype "passive"))
      (node (ref "C312") (pin "1") (pinfunction "1_1") (pintype "passive"))
      (node (ref "C313") (pin "2") (pinfunction "2_2") (pintype "passive"))
      (node (ref "C314") (pin "2") (pinfunction "2_2") (pintype "passive"))
      (node (ref "C315") (pin "1") (pinfunction "1_1") (pintype "passive"))
      (node (ref "C316") (pin "1") (pinfunction "1_1") (pintype "passive"))
      (node (ref "Q1") (pin "S") (pinfunction "S_S") (pintype "passive"))
      (node (ref "R212") (pin "2") (pinfunction "2_2") (pintype "passive"))
      (node (ref "R215") (pin "1") (pinfunction "1_1") (pintype "passive"))
      (node (ref "R216") (pin "2") (pinfunction "2_2") (pintype "passive"))
      (node (ref "R219") (pin "1") (pinfunction "1_1") (pintype "passive"))
      (node (ref "R220") (pin "2") (pinfunction "2_2") (pintype "passive"))
      (node (ref "R222") (pin "2") (pinfunction "2_2") (pintype "passive"))
      (node (ref "R225") (pin "1") (pinfunction "1_1") (pintype "passive"))
      (node (ref "R234") (pin "1") (pinfunction "1_1") (pintype "passive"))
      (node (ref "R235") (pin "2") (pinfunction "2_2") (pintype "passive"))
      (node (ref "R243") (pin "1") (pinfunction "1_1") (pintype "passive"))
      (node (ref "U37") (pin "3") (pinfunction "GND_3") (pintype "power_in"))
      (node (ref "U39") (pin "49") (pinfunction "PAD_49") (pintype "passive"))
      (node (ref "X3") (pin "2") (pinfunction "GND_2") (pintype "passive"))
      (node (ref "X3") (pin "4") (pinfunction "GND_4") (pintype "passive"))
    )
    (net (code "45") (name "Net-(D10-A)") (class "Default")
      (node (ref "D10") (pin "1") (pinfunction "A_1") (pintype "passive"))
      (node (ref "R223") (pin "2") (pinfunction "2_2") (pintype "passive"))
    )
    (net (code "46") (name "Net-(D10-K)") (class "Default")
      (node (ref "D10") (pin "2") (pinfunction "K_2") (pintype "passive"))
      (node (ref "Q1") (pin "D") (pinfunction "D_D") (pintype "passive"))
    )
    (net (code "47") (name "Net-(J24-GA1)") (class "Default")
      (node (ref "J24") (pin "14") (pinfunction "GA1_14") (pintype "passive"))
      (node (ref "R232") (pin "1") (pinfunction "1_1") (pintype "passive"))
    )
    (net (code "48") (name "Net-(J24-GA2)") (class "Default")
      (node (ref "J24") (pin "16") (pinfunction "GA2_16") (pintype "passive"))
      (node (ref "R241") (pin "1") (pinfunction "1_1") (pintype "passive"))
    )
    (net (code "49") (name "Net-(J24-TRCT1)") (class "Default")
      (node (ref "C310") (pin "1") (pinfunction "1_1") (pintype "passive"))
      (node (ref "J24") (pin "12") (pinfunction "TRCT1_12") (pintype "passive"))
    )
    (net (code "50") (name "Net-(J24-TRCT2)") (class "Default")
      (node (ref "C311") (pin "1") (pinfunction "1_1") (pintype "passive"))
      (node (ref "J24") (pin "6") (pinfunction "TRCT2_6") (pintype "passive"))
    )
    (net (code "51") (name "Net-(J24-TRCT3)") (class "Default")
      (node (ref "C313") (pin "1") (pinfunction "1_1") (pintype "passive"))
      (node (ref "J24") (pin "1") (pinfunction "TRCT3_1") (pintype "passive"))
    )
    (net (code "52") (name "Net-(J24-TRCT4)") (class "Default")
      (node (ref "C314") (pin "1") (pinfunction "1_1") (pintype "passive"))
      (node (ref "J24") (pin "7") (pinfunction "TRCT4_7") (pintype "passive"))
    )
    (net (code "53") (name "Net-(U39-JTAG_CLK)") (class "Default")
      (node (ref "R237") (pin "1") (pinfunction "1_1") (pintype "passive"))
      (node (ref "U39") (pin "20") (pinfunction "JTAG_CLK_20") (pintype "input"))
    )
    (net (code "54") (name "Net-(U39-JTAG_TDI)") (class "Default")
      (node (ref "R240") (pin "1") (pinfunction "1_1") (pintype "passive"))
      (node (ref "U39") (pin "23") (pinfunction "JTAG_TDI_23") (pintype "input"))
    )
    (net (code "55") (name "Net-(U39-JTAG_TDO)") (class "Default")
      (node (ref "R238") (pin "1") (pinfunction "1_1") (pintype "passive"))
      (node (ref "U39") (pin "21") (pinfunction "JTAG_TDO_21") (pintype "output"))
    )
    (net (code "56") (name "Net-(U39-JTAG_TMS)") (class "Default")
      (node (ref "R239") (pin "1") (pinfunction "1_1") (pintype "passive"))
      (node (ref "U39") (pin "22") (pinfunction "JTAG_TMS_22") (pintype "input"))
    )
    (net (code "57") (name "Net-(U39-RBIAS)") (class "Default")
      (node (ref "R243") (pin "2") (pinfunction "2_2") (pintype "passive"))
      (node (ref "U39") (pin "12") (pinfunction "RBIAS_12") (pintype "passive"))
    )
    (net (code "58") (name "Net-(U39-XI)") (class "Default")
      (node (ref "C315") (pin "2") (pinfunction "2_2") (pintype "passive"))
      (node (ref "U39") (pin "15") (pinfunction "XI_15") (pintype "input"))
      (node (ref "X3") (pin "1") (pinfunction "X1_1") (pintype "passive"))
    )
    (net (code "59") (name "Net-(U39-XO)") (class "Default")
      (node (ref "C316") (pin "2") (pinfunction "2_2") (pintype "passive"))
      (node (ref "U39") (pin "14") (pinfunction "XO_14") (pintype "output"))
      (node (ref "X3") (pin "3") (pinfunction "X2_3") (pintype "passive"))
    )
    (net (code "60") (name "VCCO_PSIO") (class "Default")
      (node (ref "R237") (pin "2") (pinfunction "2_2") (pintype "passive"))
      (node (ref "R238") (pin "2") (pinfunction "2_2") (pintype "passive"))
      (node (ref "R239") (pin "2") (pinfunction "2_2") (pintype "passive"))
      (node (ref "R240") (pin "2") (pinfunction "2_2") (pintype "passive"))
      (node (ref "R242") (pin "2") (pinfunction "2_2") (pintype "passive"))
    )
  )
)
